# Payloadv01.net
KiCad netlist of a schematic drawn in EAGLE
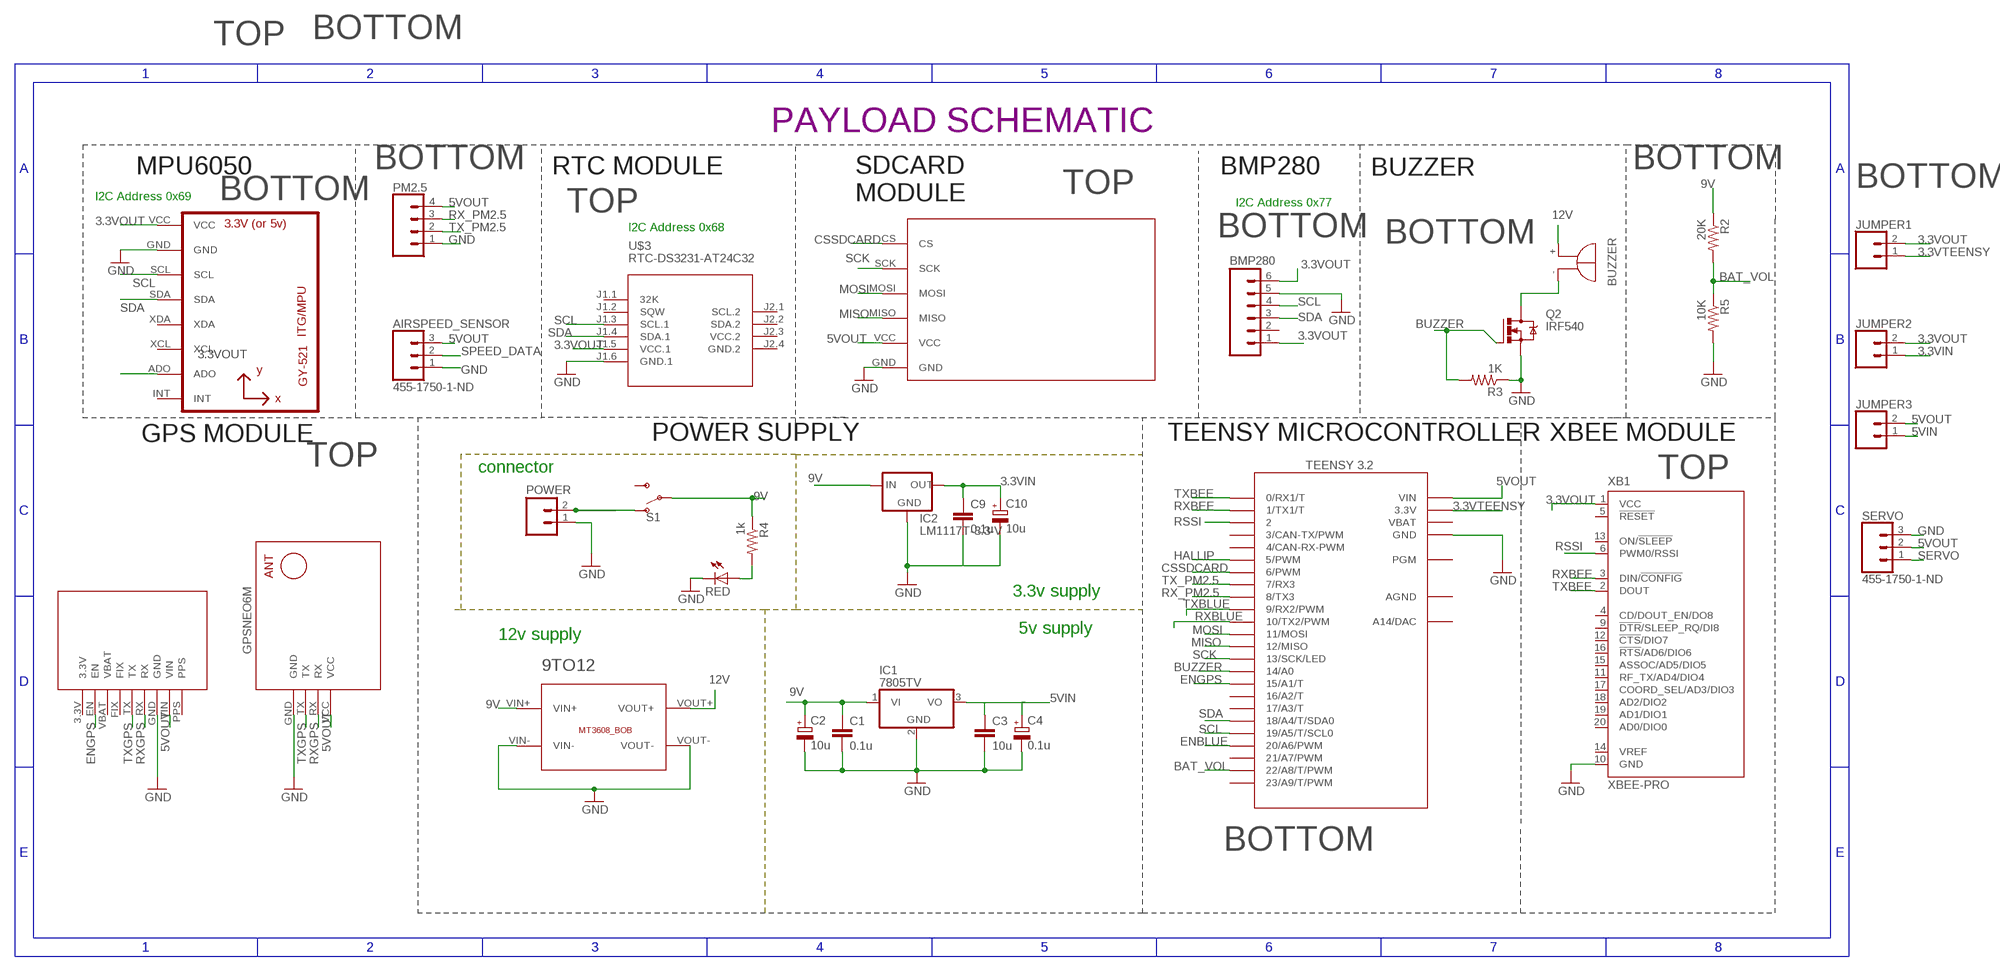
[diagram p0: schematic, sheet 1]

(export (version "E")
  (design (tool "Eeschema 10.0.6"))
  (components
    (comp (ref "9TO12")
      (value "BREAKOUTS_MT3608_BOB")
      (footprint "eagle-import:BREAKOUTS_MT3608_BOB")
      (libsource (lib "eagle-import") (part "BREAKOUTS_MT3608_BOB"))
    )
    (comp (ref "AIRSPEED_SENSOR")
      (value "455-1750-1-ND")
      (footprint "eagle-import:1X03")
      (libsource (lib "eagle-import") (part "CONN_03"))
    )
    (comp (ref "BMP280")
      (value "M06")
      (footprint "eagle-import:06P")
      (libsource (lib "eagle-import") (part "M06"))
    )
    (comp (ref "C1")
      (value "0.1u")
      (footprint "eagle-import:C025-025X050")
      (libsource (lib "eagle-import") (part "C-EU025-025X050"))
    )
    (comp (ref "C2")
      (value "10u")
      (footprint "eagle-import:E2,5-6")
      (libsource (lib "eagle-import") (part "CPOL-EUE2.5-6"))
    )
    (comp (ref "C3")
      (value "10u")
      (footprint "eagle-import:C025-025X050")
      (libsource (lib "eagle-import") (part "C-EU025-025X050"))
    )
    (comp (ref "C4")
      (value "0.1u")
      (footprint "eagle-import:E2,5-6")
      (libsource (lib "eagle-import") (part "CPOL-EUE2.5-6"))
    )
    (comp (ref "C9")
      (value "0.1u")
      (footprint "eagle-import:C025-025X050")
      (libsource (lib "eagle-import") (part "C-EU025-025X050"))
    )
    (comp (ref "C10")
      (value "10u")
      (footprint "eagle-import:E2,5-6")
      (libsource (lib "eagle-import") (part "CPOL-EUE2.5-6"))
    )
    (comp (ref "IC1")
      (value "7805TV")
      (footprint "eagle-import:TO220V")
      (libsource (lib "eagle-import") (part "78TV05"))
    )
    (comp (ref "IC2")
      (value "LM1117T-3.3-V")
      (footprint "eagle-import:TO220V")
      (libsource (lib "eagle-import") (part "LM1117T--V3.3"))
    )
    (comp (ref "JUMPER1")
      (value "CONN_02")
      (footprint "eagle-import:1X02")
      (libsource (lib "eagle-import") (part "CONN_02"))
    )
    (comp (ref "JUMPER2")
      (value "CONN_02")
      (footprint "eagle-import:1X02")
      (libsource (lib "eagle-import") (part "CONN_02"))
    )
    (comp (ref "JUMPER3")
      (value "CONN_02")
      (footprint "eagle-import:1X02")
      (libsource (lib "eagle-import") (part "CONN_02"))
    )
    (comp (ref "PM2.5")
      (value "CONN_04")
      (footprint "eagle-import:1X04")
      (libsource (lib "eagle-import") (part "CONN_04"))
    )
    (comp (ref "POWER")
      (value "CEDT_JANUARY_2015_V5_M02")
      (footprint "eagle-import:CEDT_JANUARY_2015_V5_02P")
      (libsource (lib "eagle-import") (part "CEDT_JANUARY_2015_V5_M02"))
    )
    (comp (ref "Q2")
      (value "IRF540")
      (footprint "eagle-import:TO220BV")
      (libsource (lib "eagle-import") (part "IRF540"))
    )
    (comp (ref "R2")
      (value "20K")
      (footprint "eagle-import:0204_7")
      (libsource (lib "eagle-import") (part "R-US_0204/7"))
    )
    (comp (ref "R3")
      (value "1K")
      (footprint "eagle-import:0204_7")
      (libsource (lib "eagle-import") (part "R-US_0204/7"))
    )
    (comp (ref "R4")
      (value "1k")
      (footprint "eagle-import:0204_7")
      (libsource (lib "eagle-import") (part "R-US_0204/7"))
    )
    (comp (ref "R5")
      (value "10K")
      (footprint "eagle-import:0204_7")
      (libsource (lib "eagle-import") (part "R-US_0204/7"))
    )
    (comp (ref "RED")
      (value "red")
      (footprint "eagle-import:LED3MM")
      (libsource (lib "eagle-import") (part "LED3MM"))
    )
    (comp (ref "S1")
      (value "SWITCH-SPDT-PTH-11.6X4.0MM")
      (footprint "eagle-import:SWITCH_SPDT_PTH_11.6X4.0MM")
      (libsource (lib "eagle-import") (part "SWITCH-SPDT-PTH-11.6X4.0MM"))
    )
    (comp (ref "SERVO")
      (value "455-1750-1-ND")
      (footprint "eagle-import:1X03")
      (libsource (lib "eagle-import") (part "CONN_03"))
    )
    (comp (ref "SG1")
      (value "BUZZER_EB2209A")
      (footprint "eagle-import:BUZZER_EB2209A")
      (libsource (lib "eagle-import") (part "BUZZER_EB2209A"))
    )
    (comp (ref "U$1")
      (value "GPS-RECEIVER-NEO6M")
      (footprint "eagle-import:GPS-RECEIVER-NEO6M")
      (libsource (lib "eagle-import") (part "GPS-RECEIVER-NEO6M"))
    )
    (comp (ref "U$2")
      (value "TEENSY_3.1-3.2_OUTER_ROW")
      (footprint "eagle-import:TEENSY_3.0-3.2&LC_OUTER_ROW")
      (libsource (lib "eagle-import") (part "TEENSY_3.1-3.2_OUTER_ROW"))
    )
    (comp (ref "U$3")
      (value "RTC-DS3231-AT24C32")
      (footprint "eagle-import:RTC-DS3231-AT24C32")
      (libsource (lib "eagle-import") (part "RTC-DS3231-AT24C32"))
    )
    (comp (ref "U$4")
      (value "ADAFRUIT_GPS")
      (footprint "eagle-import:ADAFRUIT_GPS")
      (libsource (lib "eagle-import") (part "ADAFRUIT_GPS"))
    )
    (comp (ref "U$5")
      (value "SDCARD")
      (footprint "eagle-import:M0SDCARDMODULE")
      (libsource (lib "eagle-import") (part "SDCARD"))
    )
    (comp (ref "U1")
      (value "GY-521MPU6050")
      (footprint "eagle-import:GY-521")
      (libsource (lib "eagle-import") (part "GY-521MPU6050"))
    )
    (comp (ref "XB1")
      (value "XBEE-PRO")
      (footprint "eagle-import:XBEE-PRO")
      (fields (field (name "MPN") "XBP24-AWI-001"))
      (libsource (lib "eagle-import") (part "XBEE-PRO"))
    )
  )
  (nets
    (net (code "1") (name "/3.3VIN") (class "Default")
      (node (ref "C10") (pin "+") (pinfunction "+_+") (pintype "passive"))
      (node (ref "C9") (pin "1") (pinfunction "1_1") (pintype "passive"))
      (node (ref "IC2") (pin "2") (pinfunction "OUT_2") (pintype "passive"))
      (node (ref "JUMPER2") (pin "1") (pinfunction "1_1") (pintype "passive"))
    )
    (net (code "2") (name "/3.3VOUT") (class "Default")
      (node (ref "BMP280") (pin "1") (pinfunction "1_1") (pintype "passive"))
      (node (ref "BMP280") (pin "6") (pinfunction "6_6") (pintype "passive"))
      (node (ref "JUMPER1") (pin "2") (pinfunction "2_2") (pintype "passive"))
      (node (ref "JUMPER2") (pin "2") (pinfunction "2_2") (pintype "passive"))
      (node (ref "U$3") (pin "J1.5") (pinfunction "VCC.1_J1.5") (pintype "power_in"))
      (node (ref "U1") (pin "ADO") (pinfunction "ADO_ADO") (pintype "bidirectional"))
      (node (ref "U1") (pin "VCC") (pinfunction "VCC_VCC") (pintype "bidirectional"))
      (node (ref "XB1") (pin "1") (pinfunction "VCC_1") (pintype "power_in"))
    )
    (net (code "3") (name "/3.3VTEENSY") (class "Default")
      (node (ref "JUMPER1") (pin "1") (pinfunction "1_1") (pintype "passive"))
      (node (ref "U$2") (pin "3.3V") (pinfunction "3.3V_3.3V") (pintype "power_in"))
      (node (ref "U$2") (pin "3.3V1") (pinfunction "3.3V_3.3V1") (pintype "power_in"))
    )
    (net (code "4") (name "/5VIN") (class "Default")
      (node (ref "C3") (pin "1") (pinfunction "1_1") (pintype "passive"))
      (node (ref "C4") (pin "+") (pinfunction "+_+") (pintype "passive"))
      (node (ref "IC1") (pin "3") (pinfunction "VO_3") (pintype "passive"))
      (node (ref "JUMPER3") (pin "1") (pinfunction "1_1") (pintype "passive"))
    )
    (net (code "5") (name "/5VOUT") (class "Default")
      (node (ref "AIRSPEED_SENSOR") (pin "3") (pinfunction "3_3") (pintype "passive"))
      (node (ref "JUMPER3") (pin "2") (pinfunction "2_2") (pintype "passive"))
      (node (ref "PM2.5") (pin "4") (pinfunction "4_4") (pintype "passive"))
      (node (ref "SERVO") (pin "2") (pinfunction "2_2") (pintype "passive"))
      (node (ref "U$1") (pin "VCC") (pinfunction "VCC_VCC") (pintype "power_in"))
      (node (ref "U$2") (pin "VIN") (pinfunction "VIN_VIN") (pintype "power_in"))
      (node (ref "U$4") (pin "VIN") (pinfunction "VIN_VIN") (pintype "bidirectional"))
      (node (ref "U$5") (pin "VCC") (pinfunction "VCC_VCC") (pintype "bidirectional"))
    )
    (net (code "6") (name "/9V") (class "Default")
      (node (ref "9TO12") (pin "VIN+") (pinfunction "VIN+_VIN+") (pintype "bidirectional"))
      (node (ref "C1") (pin "1") (pinfunction "1_1") (pintype "passive"))
      (node (ref "C2") (pin "+") (pinfunction "+_+") (pintype "passive"))
      (node (ref "IC1") (pin "1") (pinfunction "VI_1") (pintype "input"))
      (node (ref "IC2") (pin "3") (pinfunction "IN_3") (pintype "input"))
      (node (ref "R2") (pin "1") (pinfunction "1_1") (pintype "passive"))
      (node (ref "R4") (pin "1") (pinfunction "1_1") (pintype "passive"))
      (node (ref "S1") (pin "2") (pinfunction "P_2") (pintype "passive"))
    )
    (net (code "7") (name "/12V") (class "Default")
      (node (ref "9TO12") (pin "VOUT+") (pinfunction "VOUT+_VOUT+") (pintype "bidirectional"))
      (node (ref "SG1") (pin "+") (pinfunction "+_+") (pintype "passive"))
    )
    (net (code "8") (name "/AGND") (class "Default")
      (node (ref "U$2") (pin "AGND") (pinfunction "AGND_AGND") (pintype "power_in"))
    )
    (net (code "9") (name "/BAT_VOL") (class "Default")
      (node (ref "R2") (pin "2") (pinfunction "2_2") (pintype "passive"))
      (node (ref "R5") (pin "1") (pinfunction "1_1") (pintype "passive"))
      (node (ref "U$2") (pin "22/A8") (pinfunction "22/A8/T/PWM_22/A8") (pintype "bidirectional"))
    )
    (net (code "10") (name "/BUZZER") (class "Default")
      (node (ref "Q2") (pin "G") (pinfunction "G_G") (pintype "passive"))
      (node (ref "R3") (pin "2") (pinfunction "2_2") (pintype "passive"))
      (node (ref "U$2") (pin "14/A0") (pinfunction "14/A0_14/A0") (pintype "bidirectional"))
    )
    (net (code "11") (name "/CSSDCARD") (class "Default")
      (node (ref "U$2") (pin "6") (pinfunction "6/PWM_6") (pintype "bidirectional"))
      (node (ref "U$5") (pin "CS") (pinfunction "CS_CS") (pintype "bidirectional"))
    )
    (net (code "12") (name "/ENBLUE") (class "Default")
      (node (ref "U$2") (pin "20/A6") (pinfunction "20/A6/PWM_20/A6") (pintype "bidirectional"))
    )
    (net (code "13") (name "/ENGPS") (class "Default")
      (node (ref "U$2") (pin "15/A1") (pinfunction "15/A1/T_15/A1") (pintype "bidirectional"))
      (node (ref "U$4") (pin "EN") (pinfunction "EN_EN") (pintype "bidirectional"))
    )
    (net (code "14") (name "/GND.2") (class "Default")
      (node (ref "U$3") (pin "J2.4") (pinfunction "GND.2_J2.4") (pintype "power_in"))
    )
    (net (code "15") (name "/HALLIP") (class "Default")
      (node (ref "U$2") (pin "5") (pinfunction "5/PWM_5") (pintype "bidirectional"))
    )
    (net (code "16") (name "/MISO") (class "Default")
      (node (ref "U$2") (pin "12") (pinfunction "12/MISO_12") (pintype "bidirectional"))
      (node (ref "U$5") (pin "MISO") (pinfunction "MISO_MISO") (pintype "bidirectional"))
    )
    (net (code "17") (name "/MOSI") (class "Default")
      (node (ref "U$2") (pin "11") (pinfunction "11/MOSI_11") (pintype "bidirectional"))
      (node (ref "U$5") (pin "MOSI") (pinfunction "MOSI_MOSI") (pintype "bidirectional"))
    )
    (net (code "18") (name "/RSSI") (class "Default")
      (node (ref "U$2") (pin "2") (pinfunction "2_2") (pintype "bidirectional"))
      (node (ref "XB1") (pin "6") (pinfunction "PWM0/RSSI_6") (pintype "output"))
    )
    (net (code "19") (name "/RXBEE") (class "Default")
      (node (ref "U$2") (pin "1") (pinfunction "1/TX1/T_1") (pintype "bidirectional"))
      (node (ref "XB1") (pin "3") (pinfunction "DIN/~{CONFIG}_3") (pintype "input"))
    )
    (net (code "20") (name "/RXBLUE") (class "Default")
      (node (ref "U$2") (pin "10") (pinfunction "10/TX2/PWM_10") (pintype "bidirectional"))
    )
    (net (code "21") (name "/RXGPS") (class "Default")
      (node (ref "U$1") (pin "RX") (pinfunction "RX_RX") (pintype "bidirectional"))
      (node (ref "U$4") (pin "RX") (pinfunction "RX_RX") (pintype "bidirectional"))
    )
    (net (code "22") (name "/RX_PM2.5") (class "Default")
      (node (ref "PM2.5") (pin "3") (pinfunction "3_3") (pintype "passive"))
      (node (ref "U$2") (pin "8") (pinfunction "8/TX3_8") (pintype "bidirectional"))
    )
    (net (code "23") (name "/SCK") (class "Default")
      (node (ref "U$2") (pin "13") (pinfunction "13/SCK/LED_13") (pintype "bidirectional"))
      (node (ref "U$5") (pin "SCK") (pinfunction "SCK_SCK") (pintype "bidirectional"))
    )
    (net (code "24") (name "/SCL") (class "Default")
      (node (ref "BMP280") (pin "4") (pinfunction "4_4") (pintype "passive"))
      (node (ref "U$2") (pin "19/A5") (pinfunction "19/A5/T/SCL0_19/A5") (pintype "bidirectional"))
      (node (ref "U$3") (pin "J1.3") (pinfunction "SCL.1_J1.3") (pintype "bidirectional"))
      (node (ref "U1") (pin "SCL") (pinfunction "SCL_SCL") (pintype "bidirectional"))
    )
    (net (code "25") (name "/SDA") (class "Default")
      (node (ref "BMP280") (pin "3") (pinfunction "3_3") (pintype "passive"))
      (node (ref "U$2") (pin "18/A4") (pinfunction "18/A4/T/SDA0_18/A4") (pintype "bidirectional"))
      (node (ref "U$3") (pin "J1.4") (pinfunction "SDA.1_J1.4") (pintype "bidirectional"))
      (node (ref "U1") (pin "SDA") (pinfunction "SDA_SDA") (pintype "bidirectional"))
    )
    (net (code "26") (name "/SERVO") (class "Default")
      (node (ref "SERVO") (pin "1") (pinfunction "1_1") (pintype "passive"))
    )
    (net (code "27") (name "/SPEED_DATA") (class "Default")
      (node (ref "AIRSPEED_SENSOR") (pin "2") (pinfunction "2_2") (pintype "passive"))
    )
    (net (code "28") (name "/TXBEE") (class "Default")
      (node (ref "U$2") (pin "0") (pinfunction "0/RX1/T_0") (pintype "bidirectional"))
      (node (ref "XB1") (pin "2") (pinfunction "DOUT_2") (pintype "output"))
    )
    (net (code "29") (name "/TXBLUE") (class "Default")
      (node (ref "U$2") (pin "9") (pinfunction "9/RX2/PWM_9") (pintype "bidirectional"))
    )
    (net (code "30") (name "/TXGPS") (class "Default")
      (node (ref "U$1") (pin "TX") (pinfunction "TX_TX") (pintype "bidirectional"))
      (node (ref "U$4") (pin "TX") (pinfunction "TX_TX") (pintype "bidirectional"))
    )
    (net (code "31") (name "/TX_PM2.5") (class "Default")
      (node (ref "PM2.5") (pin "2") (pinfunction "2_2") (pintype "passive"))
      (node (ref "U$2") (pin "7") (pinfunction "7/RX3_7") (pintype "bidirectional"))
    )
    (net (code "32") (name "/VBAT") (class "Default")
      (node (ref "U$2") (pin "VBAT") (pinfunction "VBAT_VBAT") (pintype "power_in"))
    )
    (net (code "33") (name "/VCC.2") (class "Default")
      (node (ref "U$3") (pin "J2.3") (pinfunction "VCC.2_J2.3") (pintype "power_in"))
    )
    (net (code "34") (name "GND") (class "Default")
      (node (ref "9TO12") (pin "VIN-") (pinfunction "VIN-_VIN-") (pintype "bidirectional"))
      (node (ref "9TO12") (pin "VOUT-") (pinfunction "VOUT-_VOUT-") (pintype "bidirectional"))
      (node (ref "AIRSPEED_SENSOR") (pin "1") (pinfunction "1_1") (pintype "passive"))
      (node (ref "BMP280") (pin "5") (pinfunction "5_5") (pintype "passive"))
      (node (ref "C1") (pin "2") (pinfunction "2_2") (pintype "passive"))
      (node (ref "C10") (pin "-") (pinfunction "-_-") (pintype "passive"))
      (node (ref "C2") (pin "-") (pinfunction "-_-") (pintype "passive"))
      (node (ref "C3") (pin "2") (pinfunction "2_2") (pintype "passive"))
      (node (ref "C4") (pin "-") (pinfunction "-_-") (pintype "passive"))
      (node (ref "C9") (pin "2") (pinfunction "2_2") (pintype "passive"))
      (node (ref "IC1") (pin "2") (pinfunction "GND_2") (pintype "passive"))
      (node (ref "IC2") (pin "1") (pinfunction "GND_1") (pintype "input"))
      (node (ref "PM2.5") (pin "1") (pinfunction "1_1") (pintype "passive"))
      (node (ref "POWER") (pin "1") (pinfunction "1_1") (pintype "passive"))
      (node (ref "Q2") (pin "S") (pinfunction "S_S") (pintype "passive"))
      (node (ref "R3") (pin "1") (pinfunction "1_1") (pintype "passive"))
      (node (ref "R5") (pin "2") (pinfunction "2_2") (pintype "passive"))
      (node (ref "RED") (pin "K") (pinfunction "C_K") (pintype "passive"))
      (node (ref "SERVO") (pin "3") (pinfunction "3_3") (pintype "passive"))
      (node (ref "U$1") (pin "GND") (pinfunction "GND_GND") (pintype "bidirectional"))
      (node (ref "U$2") (pin "GND") (pinfunction "GND_GND") (pintype "power_in"))
      (node (ref "U$2") (pin "GND1") (pinfunction "GND_GND1") (pintype "power_in"))
      (node (ref "U$3") (pin "J1.6") (pinfunction "GND.1_J1.6") (pintype "power_in"))
      (node (ref "U$4") (pin "GND") (pinfunction "GND_GND") (pintype "bidirectional"))
      (node (ref "U$5") (pin "GND") (pinfunction "GND_GND") (pintype "bidirectional"))
      (node (ref "U1") (pin "GND") (pinfunction "GND_GND") (pintype "bidirectional"))
      (node (ref "XB1") (pin "10") (pinfunction "GND_10") (pintype "power_in"))
    )
    (net (code "35") (name "Net-(Q2-PadD)") (class "Default")
      (node (ref "Q2") (pin "D") (pinfunction "D_D") (pintype "passive"))
      (node (ref "SG1") (pin "-") (pinfunction "-_-") (pintype "passive"))
    )
    (net (code "36") (name "Net-(R4-Pad2)") (class "Default")
      (node (ref "R4") (pin "2") (pinfunction "2_2") (pintype "passive"))
      (node (ref "RED") (pin "A") (pinfunction "A_A") (pintype "passive"))
    )
    (net (code "37") (name "Net-(S1-O)") (class "Default")
      (node (ref "POWER") (pin "2") (pinfunction "2_2") (pintype "passive"))
      (node (ref "S1") (pin "1") (pinfunction "O_1") (pintype "passive"))
    )
    (net (code "38") (name "unconnected-(BMP280-Pad2)") (class "Default")
      (node (ref "BMP280") (pin "2") (pinfunction "2_2") (pintype "passive"))
    )
    (net (code "39") (name "unconnected-(S1-S-Pad3)") (class "Default")
      (node (ref "S1") (pin "3") (pinfunction "S_3") (pintype "passive"))
    )
    (net (code "40") (name "unconnected-(U$2-3{slash}CAN-TX{slash}PWM-Pad3)") (class "Default")
      (node (ref "U$2") (pin "3") (pinfunction "3/CAN-TX/PWM_3") (pintype "bidirectional"))
    )
    (net (code "41") (name "unconnected-(U$2-4{slash}CAN-RX-PWM-Pad4)") (class "Default")
      (node (ref "U$2") (pin "4") (pinfunction "4/CAN-RX-PWM_4") (pintype "bidirectional"))
    )
    (net (code "42") (name "unconnected-(U$2-16{slash}A2{slash}T-Pad16{slash}A2)") (class "Default")
      (node (ref "U$2") (pin "16/A2") (pinfunction "16/A2/T_16/A2") (pintype "bidirectional"))
    )
    (net (code "43") (name "unconnected-(U$2-17{slash}A3{slash}T-Pad17{slash}A3)") (class "Default")
      (node (ref "U$2") (pin "17/A3") (pinfunction "17/A3/T_17/A3") (pintype "bidirectional"))
    )
    (net (code "44") (name "unconnected-(U$2-21{slash}A7{slash}PWM-Pad21{slash}A7)") (class "Default")
      (node (ref "U$2") (pin "21/A7") (pinfunction "21/A7/PWM_21/A7") (pintype "bidirectional"))
    )
    (net (code "45") (name "unconnected-(U$2-23{slash}A9{slash}T{slash}PWM-Pad23{slash}A9)") (class "Default")
      (node (ref "U$2") (pin "23/A9") (pinfunction "23/A9/T/PWM_23/A9") (pintype "bidirectional"))
    )
    (net (code "46") (name "unconnected-(U$2-A14{slash}DAC-PadRESET{slash}DAC)") (class "Default")
      (node (ref "U$2") (pin "RESET/DAC") (pinfunction "A14/DAC_RESET/DAC") (pintype "bidirectional"))
    )
    (net (code "47") (name "unconnected-(U$2-PadPGM)") (class "Default")
      (node (ref "U$2") (pin "PGM") (pinfunction "PGM_PGM") (pintype "bidirectional"))
    )
    (net (code "48") (name "unconnected-(U$3-32K-PadJ1.1)") (class "Default")
      (node (ref "U$3") (pin "J1.1") (pinfunction "32K_J1.1") (pintype "bidirectional"))
    )
    (net (code "49") (name "unconnected-(U$3-SCL.2-PadJ2.1)") (class "Default")
      (node (ref "U$3") (pin "J2.1") (pinfunction "SCL.2_J2.1") (pintype "bidirectional"))
    )
    (net (code "50") (name "unconnected-(U$3-SDA.2-PadJ2.2)") (class "Default")
      (node (ref "U$3") (pin "J2.2") (pinfunction "SDA.2_J2.2") (pintype "bidirectional"))
    )
    (net (code "51") (name "unconnected-(U$3-SQW-PadJ1.2)") (class "Default")
      (node (ref "U$3") (pin "J1.2") (pinfunction "SQW_J1.2") (pintype "bidirectional"))
    )
    (net (code "52") (name "unconnected-(U$4-Pad3.3V)") (class "Default")
      (node (ref "U$4") (pin "3.3V") (pinfunction "3.3V_3.3V") (pintype "bidirectional"))
    )
    (net (code "53") (name "unconnected-(U$4-PadFIX)") (class "Default")
      (node (ref "U$4") (pin "FIX") (pinfunction "FIX_FIX") (pintype "bidirectional"))
    )
    (net (code "54") (name "unconnected-(U$4-PadPPS)") (class "Default")
      (node (ref "U$4") (pin "PPS") (pinfunction "PPS_PPS") (pintype "bidirectional"))
    )
    (net (code "55") (name "unconnected-(U$4-PadVBAT)") (class "Default")
      (node (ref "U$4") (pin "VBAT") (pinfunction "VBAT_VBAT") (pintype "bidirectional"))
    )
    (net (code "56") (name "unconnected-(U1-PadINT)") (class "Default")
      (node (ref "U1") (pin "INT") (pinfunction "INT_INT") (pintype "bidirectional"))
    )
    (net (code "57") (name "unconnected-(U1-PadXCL)") (class "Default")
      (node (ref "U1") (pin "XCL") (pinfunction "XCL_XCL") (pintype "bidirectional"))
    )
    (net (code "58") (name "unconnected-(U1-PadXDA)") (class "Default")
      (node (ref "U1") (pin "XDA") (pinfunction "XDA_XDA") (pintype "bidirectional"))
    )
    (net (code "59") (name "unconnected-(XB1-AD0{slash}DIO0-Pad20)") (class "Default")
      (node (ref "XB1") (pin "20") (pinfunction "AD0/DIO0_20") (pintype "bidirectional"))
    )
    (net (code "60") (name "unconnected-(XB1-AD1{slash}DIO1-Pad19)") (class "Default")
      (node (ref "XB1") (pin "19") (pinfunction "AD1/DIO1_19") (pintype "bidirectional"))
    )
    (net (code "61") (name "unconnected-(XB1-AD2{slash}DIO2-Pad18)") (class "Default")
      (node (ref "XB1") (pin "18") (pinfunction "AD2/DIO2_18") (pintype "bidirectional"))
    )
    (net (code "62") (name "unconnected-(XB1-ASSOC{slash}AD5{slash}DIO5-Pad15)") (class "Default")
      (node (ref "XB1") (pin "15") (pinfunction "ASSOC/AD5/DIO5_15") (pintype "bidirectional"))
    )
    (net (code "63") (name "unconnected-(XB1-CD{slash}DOUT_EN{slash}DO8-Pad4)") (class "Default")
      (node (ref "XB1") (pin "4") (pinfunction "CD/DOUT_EN/DO8_4") (pintype "output"))
    )
    (net (code "64") (name "unconnected-(XB1-COORD_SEL{slash}AD3{slash}DIO3-Pad17)") (class "Default")
      (node (ref "XB1") (pin "17") (pinfunction "COORD_SEL/AD3/DIO3_17") (pintype "bidirectional"))
    )
    (net (code "65") (name "unconnected-(XB1-ON{slash}~{SLEEP}-Pad13)") (class "Default")
      (node (ref "XB1") (pin "13") (pinfunction "ON/~{SLEEP}_13") (pintype "output"))
    )
    (net (code "66") (name "unconnected-(XB1-RF_TX{slash}AD4{slash}DIO4-Pad11)") (class "Default")
      (node (ref "XB1") (pin "11") (pinfunction "RF_TX/AD4/DIO4_11") (pintype "bidirectional"))
    )
    (net (code "67") (name "unconnected-(XB1-VREF-Pad14)") (class "Default")
      (node (ref "XB1") (pin "14") (pinfunction "VREF_14") (pintype "input"))
    )
    (net (code "68") (name "unconnected-(XB1-~{CTS}{slash}DIO7-Pad12)") (class "Default")
      (node (ref "XB1") (pin "12") (pinfunction "~{CTS}/DIO7_12") (pintype "bidirectional"))
    )
    (net (code "69") (name "unconnected-(XB1-~{DTR}{slash}SLEEP_RQ{slash}DI8-Pad9)") (class "Default")
      (node (ref "XB1") (pin "9") (pinfunction "~{DTR}/SLEEP_RQ/DI8_9") (pintype "bidirectional"))
    )
    (net (code "70") (name "unconnected-(XB1-~{RESET}-Pad5)") (class "Default")
      (node (ref "XB1") (pin "5") (pinfunction "~{RESET}_5") (pintype "input"))
    )
    (net (code "71") (name "unconnected-(XB1-~{RTS}{slash}AD6{slash}DIO6-Pad16)") (class "Default")
      (node (ref "XB1") (pin "16") (pinfunction "~{RTS}/AD6/DIO6_16") (pintype "bidirectional"))
    )
  )
)
